# rfm.net
KiCad netlist of a schematic drawn in Altium Designer
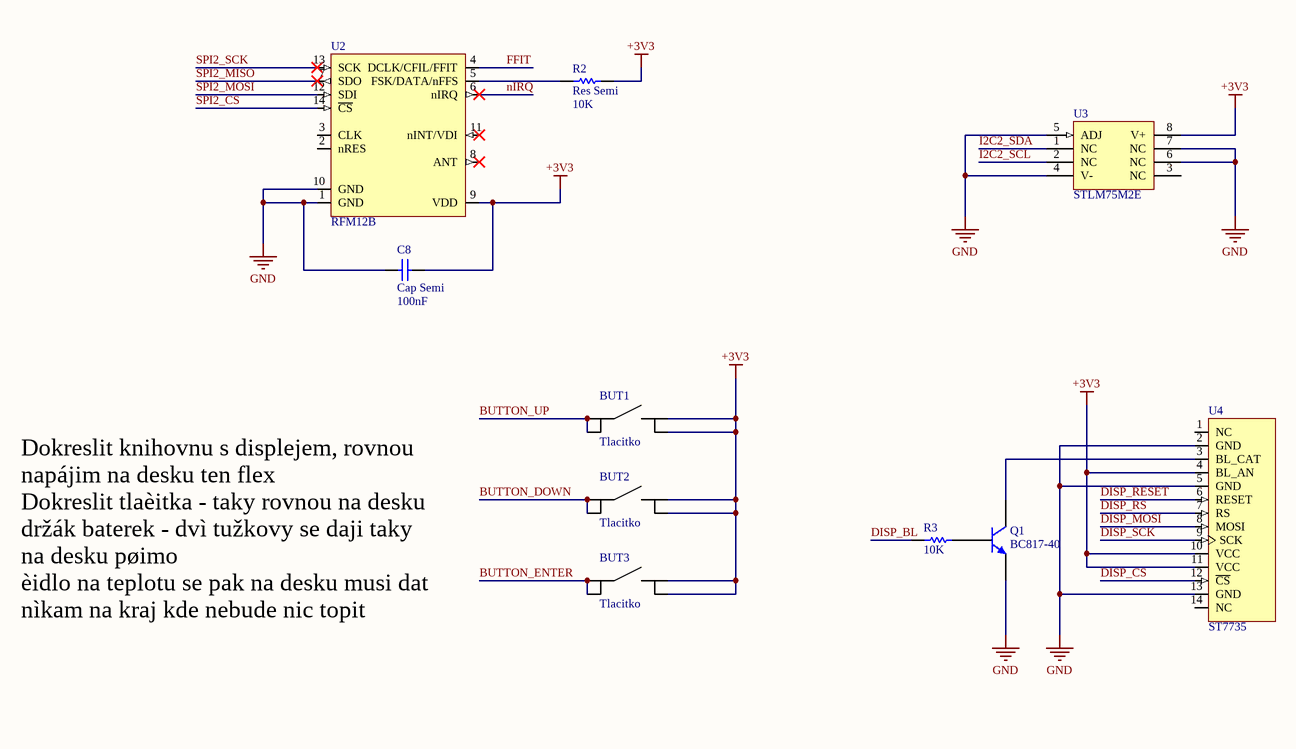
[diagram p0: rfm.SchDoc]

(export (version "E")
  (design (tool "Eeschema 10.0.6"))
  (components
    (comp (ref "BUT1")
      (value "Tlacitko")
      (footprint "TLACITKO")
      (libsource (lib "Integrated_Library1") (part "Tlacitko"))
    )
    (comp (ref "BUT2")
      (value "Tlacitko")
      (footprint "TLACITKO")
      (libsource (lib "Integrated_Library1") (part "Tlacitko"))
    )
    (comp (ref "BUT3")
      (value "Tlacitko")
      (footprint "TLACITKO")
      (libsource (lib "Integrated_Library1") (part "Tlacitko"))
    )
    (comp (ref "C8")
      (value "Cap Semi")
      (footprint "CAPC3216L")
      (description "Capacitor (Semiconductor SIM Model)")
      (fields (field (name "ALTIUM_VALUE") "100nF") (field (name "PUBLISHER") "Altium Limited"))
      (libsource (lib "Miscellaneous Devices") (part "Cap Semi"))
    )
    (comp (ref "Q1")
      (value "BC817-40")
      (footprint "SOT-23A")
      (description "NPN General Purpose Amplifier")
      (fields (field (name "PUBLISHER") "Altium Limited"))
      (libsource (lib "FSC Discrete BJT") (part "BC817-40"))
    )
    (comp (ref "R2")
      (value "Res Semi")
      (footprint "RESC2012L")
      (description "Semiconductor Resistor")
      (fields (field (name "ALTIUM_VALUE") "10K") (field (name "PUBLISHER") "Altium Limited"))
      (libsource (lib "Miscellaneous Devices") (part "Res Semi"))
    )
    (comp (ref "R3")
      (value "10K")
      (footprint "RESC2012L")
      (description "Semiconductor Resistor")
      (fields (field (name "Comment") "Res Semi") (field (name "PUBLISHER") "Altium Limited"))
      (libsource (lib "altium-import") (part "root_2__Miscellaneous Devices.IntLib"))
    )
    (comp (ref "U2")
      (value "RFM12B")
      (footprint "PCBComponent_1")
      (libsource (lib "Integrated_Library1") (part "RFM12B"))
    )
    (comp (ref "U3")
      (value "STLM75M2E")
      (footprint "SO8_M")
      (description "Precision Temperature Sensor")
      (fields (field (name "PUBLISHER") "Altium Limited"))
      (libsource (lib "ST Sensor Temperature Sensor") (part "LM335AD"))
    )
    (comp (ref "U4")
      (value "ST7735")
      (footprint "ST7735_DESKA")
      (libsource (lib "Integrated_Library1") (part "ST7735"))
    )
  )
  (nets
    (net (code "1") (name "+3V3") (class "Default")
      (node (ref "BUT1") (pin "3") (pinfunction "3_3") (pintype "passive"))
      (node (ref "BUT1") (pin "4") (pinfunction "17_4") (pintype "passive"))
      (node (ref "BUT2") (pin "3") (pinfunction "3_3") (pintype "passive"))
      (node (ref "BUT2") (pin "4") (pinfunction "17_4") (pintype "passive"))
      (node (ref "BUT3") (pin "3") (pinfunction "3_3") (pintype "passive"))
      (node (ref "BUT3") (pin "4") (pinfunction "17_4") (pintype "passive"))
      (node (ref "C8") (pin "1") (pinfunction "1_1") (pintype "passive"))
      (node (ref "R2") (pin "2") (pinfunction "2_2") (pintype "passive"))
      (node (ref "U2") (pin "9") (pinfunction "VDD_9") (pintype "power_in"))
      (node (ref "U3") (pin "8") (pinfunction "V+_8") (pintype "power_in"))
      (node (ref "U4") (pin "10") (pinfunction "VCC_10") (pintype "power_in"))
      (node (ref "U4") (pin "11") (pinfunction "VCC_11") (pintype "power_in"))
      (node (ref "U4") (pin "4") (pinfunction "BL_AN_4") (pintype "power_in"))
    )
    (net (code "2") (name "/BUTTON_DOWN") (class "Default")
      (node (ref "BUT2") (pin "1") (pinfunction "15_1") (pintype "passive"))
      (node (ref "BUT2") (pin "2") (pinfunction "18_2") (pintype "passive"))
    )
    (net (code "3") (name "/BUTTON_ENTER") (class "Default")
      (node (ref "BUT3") (pin "1") (pinfunction "15_1") (pintype "passive"))
      (node (ref "BUT3") (pin "2") (pinfunction "18_2") (pintype "passive"))
    )
    (net (code "4") (name "/BUTTON_UP") (class "Default")
      (node (ref "BUT1") (pin "1") (pinfunction "15_1") (pintype "passive"))
      (node (ref "BUT1") (pin "2") (pinfunction "18_2") (pintype "passive"))
    )
    (net (code "5") (name "/DISP_BL") (class "Default")
      (node (ref "R3") (pin "2") (pinfunction "2_2") (pintype "passive"))
    )
    (net (code "6") (name "/DISP_CS") (class "Default")
      (node (ref "U4") (pin "12") (pinfunction "~{CS}_12") (pintype "input"))
    )
    (net (code "7") (name "/DISP_MOSI") (class "Default")
      (node (ref "U4") (pin "8") (pinfunction "MOSI_8") (pintype "input"))
    )
    (net (code "8") (name "/DISP_RESET") (class "Default")
      (node (ref "U4") (pin "6") (pinfunction "RESET_6") (pintype "input"))
    )
    (net (code "9") (name "/DISP_RS") (class "Default")
      (node (ref "U4") (pin "7") (pinfunction "RS_7") (pintype "input"))
    )
    (net (code "10") (name "/DISP_SCK") (class "Default")
      (node (ref "U4") (pin "9") (pinfunction "SCK_9") (pintype "input"))
    )
    (net (code "11") (name "/FFIT") (class "Default")
      (node (ref "U2") (pin "4") (pinfunction "DCLK/CFIL/FFIT_4") (pintype "bidirectional"))
    )
    (net (code "12") (name "/I2C2_SCL") (class "Default")
      (node (ref "U3") (pin "2") (pinfunction "NC_2") (pintype "passive"))
    )
    (net (code "13") (name "/I2C2_SDA") (class "Default")
      (node (ref "U3") (pin "1") (pinfunction "NC_1") (pintype "passive"))
    )
    (net (code "14") (name "/SPI2_CS") (class "Default")
      (node (ref "U2") (pin "14") (pinfunction "~{CS}_14") (pintype "input"))
    )
    (net (code "15") (name "/SPI2_MISO") (class "Default")
      (node (ref "U2") (pin "7") (pinfunction "SDO_7") (pintype "output+no_connect"))
    )
    (net (code "16") (name "/SPI2_MOSI") (class "Default")
      (node (ref "U2") (pin "12") (pinfunction "SDI_12") (pintype "input"))
    )
    (net (code "17") (name "/SPI2_SCK") (class "Default")
      (node (ref "U2") (pin "13") (pinfunction "SCK_13") (pintype "input+no_connect"))
    )
    (net (code "18") (name "/nIRQ") (class "Default")
      (node (ref "U2") (pin "6") (pinfunction "nIRQ_6") (pintype "output+no_connect"))
    )
    (net (code "19") (name "GND") (class "Default")
      (node (ref "C8") (pin "2") (pinfunction "2_2") (pintype "passive"))
      (node (ref "Q1") (pin "2") (pinfunction "E_2") (pintype "passive"))
      (node (ref "U2") (pin "1") (pinfunction "GND_1") (pintype "power_in"))
      (node (ref "U2") (pin "10") (pinfunction "GND_10") (pintype "power_in"))
      (node (ref "U3") (pin "4") (pinfunction "V-_4") (pintype "power_in"))
      (node (ref "U3") (pin "5") (pinfunction "ADJ_5") (pintype "input"))
      (node (ref "U3") (pin "6") (pinfunction "NC_6") (pintype "passive"))
      (node (ref "U3") (pin "7") (pinfunction "NC_7") (pintype "passive"))
      (node (ref "U4") (pin "13") (pinfunction "GND_13") (pintype "power_in"))
      (node (ref "U4") (pin "2") (pinfunction "GND_2") (pintype "power_in"))
      (node (ref "U4") (pin "5") (pinfunction "GND_5") (pintype "power_in"))
    )
    (net (code "20") (name "Net-(Q1-B)") (class "Default")
      (node (ref "Q1") (pin "1") (pinfunction "B_1") (pintype "passive"))
      (node (ref "R3") (pin "1") (pinfunction "1_1") (pintype "passive"))
    )
    (net (code "21") (name "Net-(Q1-C)") (class "Default")
      (node (ref "Q1") (pin "3") (pinfunction "C_3") (pintype "passive"))
      (node (ref "U4") (pin "3") (pinfunction "BL_CAT_3") (pintype "power_in"))
    )
    (net (code "22") (name "Net-(U2-FSK{slash}DATA{slash}nFFS)") (class "Default")
      (node (ref "R2") (pin "1") (pinfunction "1_1") (pintype "passive"))
      (node (ref "U2") (pin "5") (pinfunction "FSK/DATA/nFFS_5") (pintype "bidirectional"))
    )
    (net (code "23") (name "unconnected-(U2-ANT-Pad8)") (class "Default")
      (node (ref "U2") (pin "8") (pinfunction "ANT_8") (pintype "output+no_connect"))
    )
    (net (code "24") (name "unconnected-(U2-CLK-Pad3)") (class "Default")
      (node (ref "U2") (pin "3") (pinfunction "CLK_3") (pintype "bidirectional"))
    )
    (net (code "25") (name "unconnected-(U2-nINT{slash}VDI-Pad11)") (class "Default")
      (node (ref "U2") (pin "11") (pinfunction "nINT/VDI_11") (pintype "input+no_connect"))
    )
    (net (code "26") (name "unconnected-(U2-nRES-Pad2)") (class "Default")
      (node (ref "U2") (pin "2") (pinfunction "nRES_2") (pintype "bidirectional"))
    )
    (net (code "27") (name "unconnected-(U3-NC-Pad3)") (class "Default")
      (node (ref "U3") (pin "3") (pinfunction "NC_3") (pintype "passive"))
    )
    (net (code "28") (name "unconnected-(U4-NC-Pad1)") (class "Default")
      (node (ref "U4") (pin "1") (pinfunction "NC_1") (pintype "passive"))
    )
    (net (code "29") (name "unconnected-(U4-NC-Pad14)") (class "Default")
      (node (ref "U4") (pin "14") (pinfunction "NC_14") (pintype "passive"))
    )
  )
)
